# EDU_High-Speed-Design_CPU_MMC-Card.net
KiCad netlist of a schematic drawn in Altium Designer
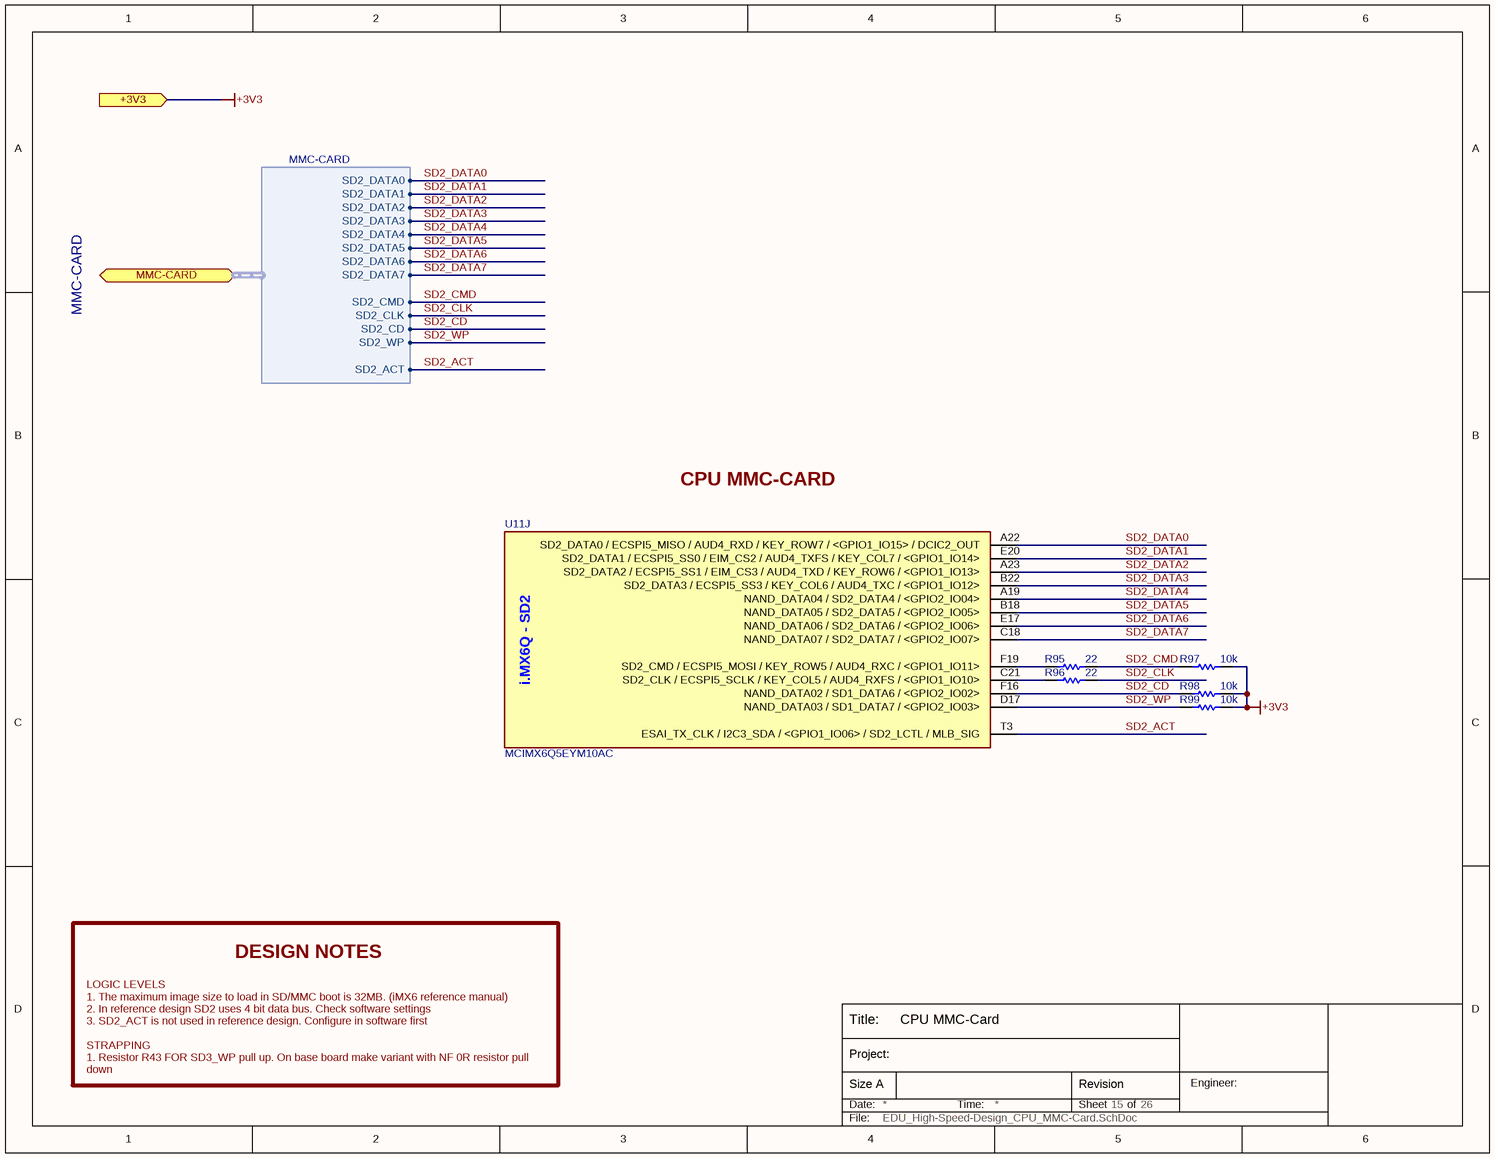
[diagram p0: EDU_High-Speed-Design_CPU_MMC-Card.SchDoc]

(export (version "E")
  (design (tool "Eeschema 10.0.6"))
  (components
    (comp (ref "R95")
      (value "22")
      (footprint "R0402")
      (description "RES 22.0 OHM 1/16W 1% 0402 SMD")
      (libsource (lib "EDU_High-Speed-Design") (part "RC0402FR-0722RL"))
    )
    (comp (ref "R96")
      (value "22")
      (footprint "R0402")
      (description "RES 22.0 OHM 1/16W 1% 0402 SMD")
      (libsource (lib "EDU_High-Speed-Design") (part "RC0402FR-0722RL"))
    )
    (comp (ref "R97")
      (value "10k")
      (footprint "R0402")
      (description "RES 10.0K OHM 1/16W 1% 0402 SMD")
      (libsource (lib "EDU_High-Speed-Design") (part "RC0402FR-0710KL"))
    )
    (comp (ref "R98")
      (value "10k")
      (footprint "R0402")
      (description "RES 10.0K OHM 1/16W 1% 0402 SMD")
      (libsource (lib "EDU_High-Speed-Design") (part "RC0402FR-0710KL"))
    )
    (comp (ref "R99")
      (value "10k")
      (footprint "R0402")
      (description "RES 10.0K OHM 1/16W 1% 0402 SMD")
      (libsource (lib "EDU_High-Speed-Design") (part "RC0402FR-0710KL"))
    )
    (comp (ref "U11")
      (value "MCIMX6Q5EYM10AC")
      (footprint "MCIMX6Q5EYM10AC")
      (description "IC MCU 32BIT ARM QUAD 624FCBGA")
      (libsource (lib "EDU_High-Speed-Design") (part "MCIMX6Q5EYM10AC"))
    )
  )
  (nets
    (net (code "2") (name "+3V3") (class "Default")
      (node (ref "R97") (pin "2") (pinfunction "2_2") (pintype "passive"))
      (node (ref "R98") (pin "2") (pinfunction "2_2") (pintype "passive"))
      (node (ref "R99") (pin "2") (pinfunction "2_2") (pintype "passive"))
    )
    (net (code "3") (name "/SD2_ACT") (class "Default")
      (node (ref "U11") (pin "T3") (pinfunction "ESAI_TX_CLK_/_I2C3_SDA_/_<GPIO1_IO06>_/_SD2_LCTL_/_MLB_SIG_T3") (pintype "passive"))
    )
    (net (code "4") (name "/SD2_CD") (class "Default")
      (node (ref "R98") (pin "1") (pinfunction "1_1") (pintype "passive"))
      (node (ref "U11") (pin "F16") (pinfunction "NAND_DATA02_/_SD1_DATA6_/_<GPIO2_IO02>_F16") (pintype "passive"))
    )
    (net (code "5") (name "/SD2_CLK") (class "Default")
      (node (ref "R96") (pin "1") (pinfunction "1_1") (pintype "passive"))
    )
    (net (code "6") (name "/SD2_CMD") (class "Default")
      (node (ref "R95") (pin "1") (pinfunction "1_1") (pintype "passive"))
      (node (ref "R97") (pin "1") (pinfunction "1_1") (pintype "passive"))
    )
    (net (code "7") (name "/SD2_DATA0") (class "Default")
      (node (ref "U11") (pin "A22") (pinfunction "SD2_DATA0_/_ECSPI5_MISO_/_AUD4_RXD_/_KEY_ROW7_/_<GPIO1_IO15>_/_DCIC2_OUT_A22") (pintype "passive"))
    )
    (net (code "8") (name "/SD2_DATA1") (class "Default")
      (node (ref "U11") (pin "E20") (pinfunction "SD2_DATA1_/_ECSPI5_SS0_/_EIM_CS2_/_AUD4_TXFS_/_KEY_COL7_/_<GPIO1_IO14>_E20") (pintype "passive"))
    )
    (net (code "9") (name "/SD2_DATA2") (class "Default")
      (node (ref "U11") (pin "A23") (pinfunction "SD2_DATA2_/_ECSPI5_SS1_/_EIM_CS3_/_AUD4_TXD_/_KEY_ROW6_/_<GPIO1_IO13>_A23") (pintype "passive"))
    )
    (net (code "10") (name "/SD2_DATA3") (class "Default")
      (node (ref "U11") (pin "B22") (pinfunction "SD2_DATA3_/_ECSPI5_SS3_/_KEY_COL6_/_AUD4_TXC_/_<GPIO1_IO12>_B22") (pintype "passive"))
    )
    (net (code "11") (name "/SD2_DATA4") (class "Default")
      (node (ref "U11") (pin "A19") (pinfunction "NAND_DATA04_/_SD2_DATA4_/_<GPIO2_IO04>_A19") (pintype "passive"))
    )
    (net (code "12") (name "/SD2_DATA5") (class "Default")
      (node (ref "U11") (pin "B18") (pinfunction "NAND_DATA05_/_SD2_DATA5_/_<GPIO2_IO05>_B18") (pintype "passive"))
    )
    (net (code "13") (name "/SD2_DATA6") (class "Default")
      (node (ref "U11") (pin "E17") (pinfunction "NAND_DATA06_/_SD2_DATA6_/_<GPIO2_IO06>_E17") (pintype "passive"))
    )
    (net (code "14") (name "/SD2_DATA7") (class "Default")
      (node (ref "U11") (pin "C18") (pinfunction "NAND_DATA07_/_SD2_DATA7_/_<GPIO2_IO07>_C18") (pintype "passive"))
    )
    (net (code "15") (name "/SD2_WP") (class "Default")
      (node (ref "R99") (pin "1") (pinfunction "1_1") (pintype "passive"))
      (node (ref "U11") (pin "D17") (pinfunction "NAND_DATA03_/_SD1_DATA7_/_<GPIO2_IO03>_D17") (pintype "passive"))
    )
    (net (code "17") (name "Net-(U11J-SD2_CLK_{slash}_ECSPI5_SCLK_{slash}_KEY_COL5_{slash}_AUD4_RXFS_{slash}_<GPIO1_IO10>)") (class "Default")
      (node (ref "R96") (pin "2") (pinfunction "2_2") (pintype "passive"))
      (node (ref "U11") (pin "C21") (pinfunction "SD2_CLK_/_ECSPI5_SCLK_/_KEY_COL5_/_AUD4_RXFS_/_<GPIO1_IO10>_C21") (pintype "passive"))
    )
    (net (code "18") (name "Net-(U11J-SD2_CMD_{slash}_ECSPI5_MOSI_{slash}_KEY_ROW5_{slash}_AUD4_RXC_{slash}_<GPIO1_IO11>)") (class "Default")
      (node (ref "R95") (pin "2") (pinfunction "2_2") (pintype "passive"))
      (node (ref "U11") (pin "F19") (pinfunction "SD2_CMD_/_ECSPI5_MOSI_/_KEY_ROW5_/_AUD4_RXC_/_<GPIO1_IO11>_F19") (pintype "passive"))
    )
  )
)
